# 15_-_ETHERNET_PHY.net
KiCad netlist of a schematic drawn in Altium Designer
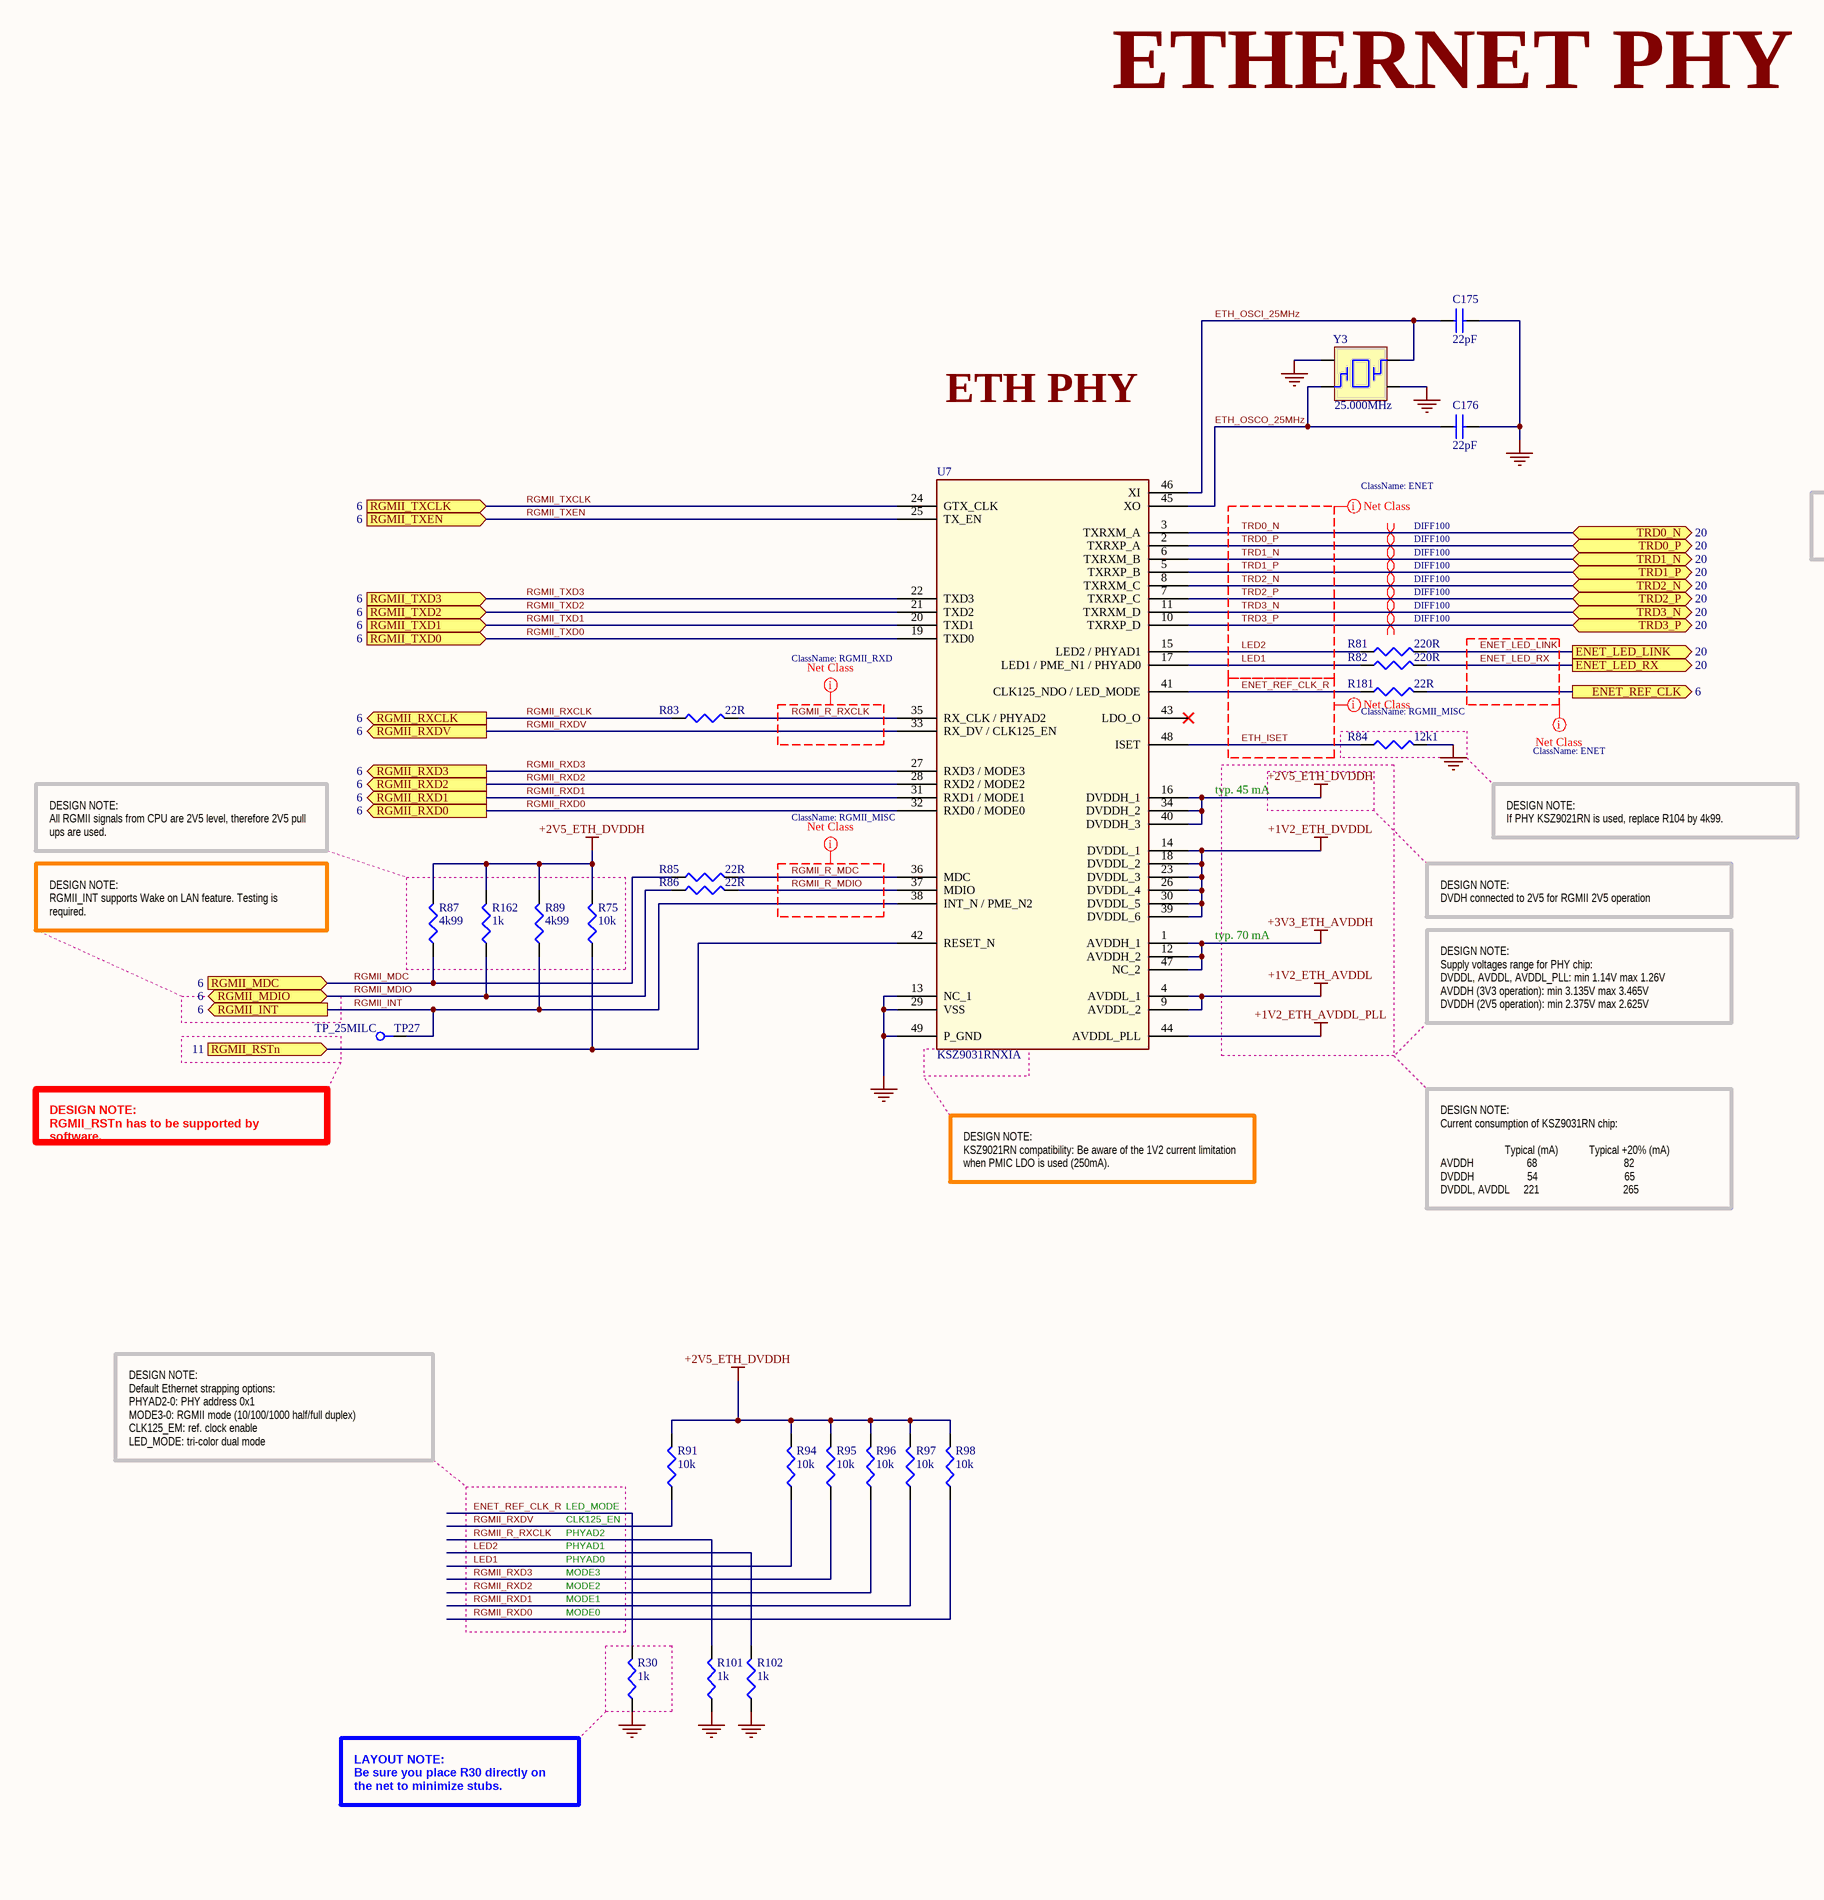
[diagram p0: [15] - ETHERNET PHY.SchDoc, left]
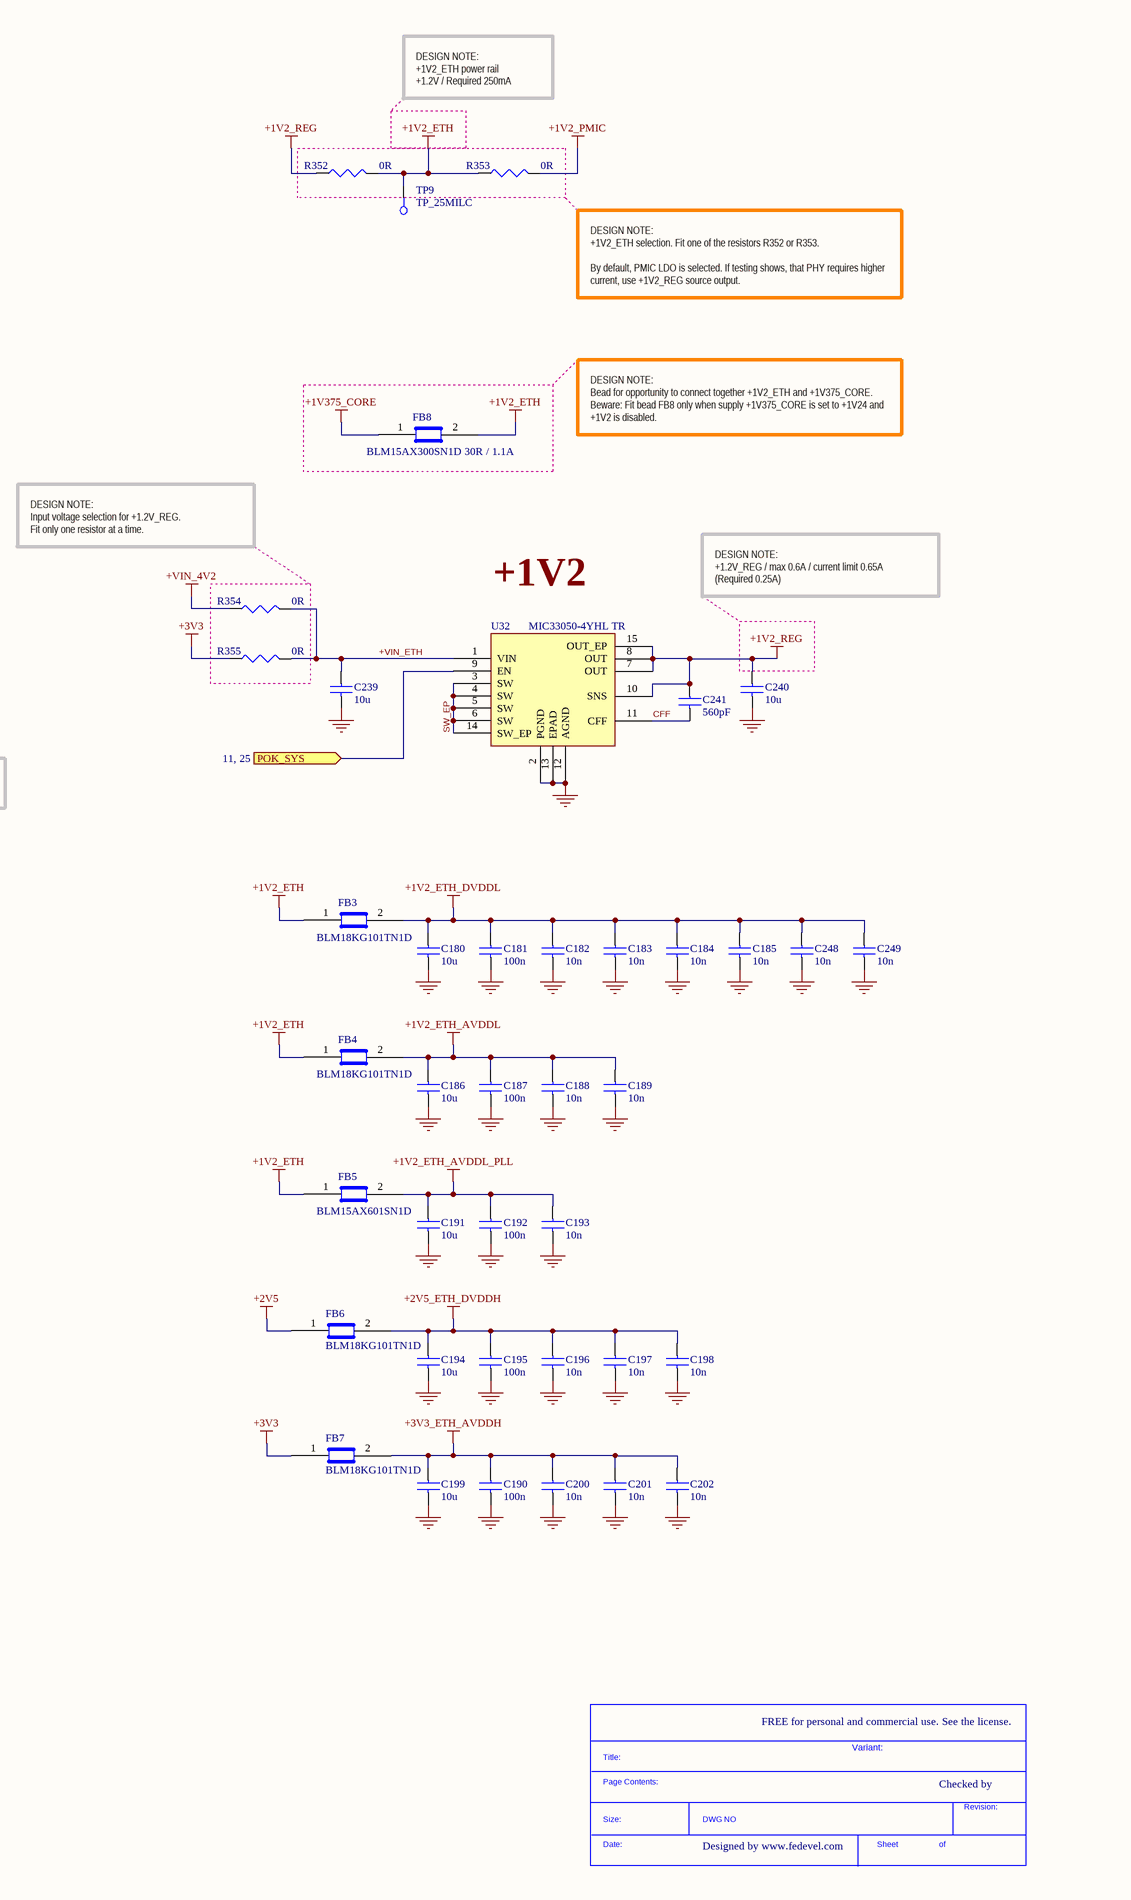
[diagram p1: [15] - ETHERNET PHY.SchDoc, right]

(export (version "E")
  (design (tool "Eeschema 10.0.6"))
  (components
    (comp (ref "C175")
      (value "22pF")
      (footprint "C0402")
      (description "CAP CER 22PF 50V C0G 5% 0402")
      (fields
        (field (name "MANUFACTURER") "TDK Corporation")
        (field (name "MANUFACTURER PART NUMBER") "C1005C0G1H220J")
      )
      (libsource (lib "Integrated_Library_FEDEVEL_APR_2015") (part "C1005C0G1H220J"))
    )
    (comp (ref "C176")
      (value "22pF")
      (footprint "C0402")
      (description "CAP CER 22PF 50V C0G 5% 0402")
      (fields
        (field (name "MANUFACTURER") "TDK Corporation")
        (field (name "MANUFACTURER PART NUMBER") "C1005C0G1H220J")
      )
      (libsource (lib "Integrated_Library_FEDEVEL_APR_2015") (part "C1005C0G1H220J"))
    )
    (comp (ref "C180")
      (value "10u")
      (footprint "C0603")
      (description "CAP CER 10UF 6.3V X5R 20% 0603")
      (fields
        (field (name "MANUFACTURER") "TDK Corporation")
        (field (name "MANUFACTURER PART NUMBER") "C1608X5R0J106M")
      )
      (libsource (lib "Integrated_Library_FEDEVEL_APR_2015") (part "C1608X5R0J106M"))
    )
    (comp (ref "C181")
      (value "100n")
      (footprint "C0402")
      (description "CAP CER .10UF 50V X5R 10% 0402")
      (fields
        (field (name "MANUFACTURER") "TDK Corporation")
        (field (name "MANUFACTURER PART NUMBER") "C1005X5R1H104K")
      )
      (libsource (lib "Integrated_Library_FEDEVEL_APR_2015") (part "C1005X5R1H104K"))
    )
    (comp (ref "C182")
      (value "10n")
      (footprint "C0402")
      (description "CAP CER 10000PF 50V 10% X7R 0402")
      (fields
        (field (name "MANUFACTURER") "TDK Corporation")
        (field (name "MANUFACTURER PART NUMBER") "C1005X7R1H103K")
      )
      (libsource (lib "Integrated_Library_FEDEVEL_APR_2015") (part "C1005X7R1H103K"))
    )
    (comp (ref "C183")
      (value "10n")
      (footprint "C0402")
      (description "CAP CER 10000PF 50V 10% X7R 0402")
      (fields
        (field (name "MANUFACTURER") "TDK Corporation")
        (field (name "MANUFACTURER PART NUMBER") "C1005X7R1H103K")
      )
      (libsource (lib "Integrated_Library_FEDEVEL_APR_2015") (part "C1005X7R1H103K"))
    )
    (comp (ref "C184")
      (value "10n")
      (footprint "C0402")
      (description "CAP CER 10000PF 50V 10% X7R 0402")
      (fields
        (field (name "MANUFACTURER") "TDK Corporation")
        (field (name "MANUFACTURER PART NUMBER") "C1005X7R1H103K")
      )
      (libsource (lib "Integrated_Library_FEDEVEL_APR_2015") (part "C1005X7R1H103K"))
    )
    (comp (ref "C185")
      (value "10n")
      (footprint "C0402")
      (description "CAP CER 10000PF 50V 10% X7R 0402")
      (fields
        (field (name "MANUFACTURER") "TDK Corporation")
        (field (name "MANUFACTURER PART NUMBER") "C1005X7R1H103K")
      )
      (libsource (lib "Integrated_Library_FEDEVEL_APR_2015") (part "C1005X7R1H103K"))
    )
    (comp (ref "C186")
      (value "10u")
      (footprint "C0603")
      (description "CAP CER 10UF 6.3V X5R 20% 0603")
      (fields
        (field (name "MANUFACTURER") "TDK Corporation")
        (field (name "MANUFACTURER PART NUMBER") "C1608X5R0J106M")
      )
      (libsource (lib "Integrated_Library_FEDEVEL_APR_2015") (part "C1608X5R0J106M"))
    )
    (comp (ref "C187")
      (value "100n")
      (footprint "C0402")
      (description "CAP CER .10UF 50V X5R 10% 0402")
      (fields
        (field (name "MANUFACTURER") "TDK Corporation")
        (field (name "MANUFACTURER PART NUMBER") "C1005X5R1H104K")
      )
      (libsource (lib "Integrated_Library_FEDEVEL_APR_2015") (part "C1005X5R1H104K"))
    )
    (comp (ref "C188")
      (value "10n")
      (footprint "C0402")
      (description "CAP CER 10000PF 50V 10% X7R 0402")
      (fields
        (field (name "MANUFACTURER") "TDK Corporation")
        (field (name "MANUFACTURER PART NUMBER") "C1005X7R1H103K")
      )
      (libsource (lib "Integrated_Library_FEDEVEL_APR_2015") (part "C1005X7R1H103K"))
    )
    (comp (ref "C189")
      (value "10n")
      (footprint "C0402")
      (description "CAP CER 10000PF 50V 10% X7R 0402")
      (fields
        (field (name "MANUFACTURER") "TDK Corporation")
        (field (name "MANUFACTURER PART NUMBER") "C1005X7R1H103K")
      )
      (libsource (lib "Integrated_Library_FEDEVEL_APR_2015") (part "C1005X7R1H103K"))
    )
    (comp (ref "C190")
      (value "100n")
      (footprint "C0402")
      (description "CAP CER .10UF 50V X5R 10% 0402")
      (fields
        (field (name "MANUFACTURER") "TDK Corporation")
        (field (name "MANUFACTURER PART NUMBER") "C1005X5R1H104K")
      )
      (libsource (lib "Integrated_Library_FEDEVEL_APR_2015") (part "C1005X5R1H104K"))
    )
    (comp (ref "C191")
      (value "10u")
      (footprint "C0603")
      (description "CAP CER 10UF 6.3V X5R 20% 0603")
      (fields
        (field (name "MANUFACTURER") "TDK Corporation")
        (field (name "MANUFACTURER PART NUMBER") "C1608X5R0J106M")
      )
      (libsource (lib "Integrated_Library_FEDEVEL_APR_2015") (part "C1608X5R0J106M"))
    )
    (comp (ref "C192")
      (value "100n")
      (footprint "C0402")
      (description "CAP CER .10UF 50V X5R 10% 0402")
      (fields
        (field (name "MANUFACTURER") "TDK Corporation")
        (field (name "MANUFACTURER PART NUMBER") "C1005X5R1H104K")
      )
      (libsource (lib "Integrated_Library_FEDEVEL_APR_2015") (part "C1005X5R1H104K"))
    )
    (comp (ref "C193")
      (value "10n")
      (footprint "C0402")
      (description "CAP CER 10000PF 50V 10% X7R 0402")
      (fields
        (field (name "MANUFACTURER") "TDK Corporation")
        (field (name "MANUFACTURER PART NUMBER") "C1005X7R1H103K")
      )
      (libsource (lib "Integrated_Library_FEDEVEL_APR_2015") (part "C1005X7R1H103K"))
    )
    (comp (ref "C194")
      (value "10u")
      (footprint "C0603")
      (description "CAP CER 10UF 6.3V X5R 20% 0603")
      (fields
        (field (name "MANUFACTURER") "TDK Corporation")
        (field (name "MANUFACTURER PART NUMBER") "C1608X5R0J106M")
      )
      (libsource (lib "Integrated_Library_FEDEVEL_APR_2015") (part "C1608X5R0J106M"))
    )
    (comp (ref "C195")
      (value "100n")
      (footprint "C0402")
      (description "CAP CER .10UF 50V X5R 10% 0402")
      (fields
        (field (name "MANUFACTURER") "TDK Corporation")
        (field (name "MANUFACTURER PART NUMBER") "C1005X5R1H104K")
      )
      (libsource (lib "Integrated_Library_FEDEVEL_APR_2015") (part "C1005X5R1H104K"))
    )
    (comp (ref "C196")
      (value "10n")
      (footprint "C0402")
      (description "CAP CER 10000PF 50V 10% X7R 0402")
      (fields
        (field (name "MANUFACTURER") "TDK Corporation")
        (field (name "MANUFACTURER PART NUMBER") "C1005X7R1H103K")
      )
      (libsource (lib "Integrated_Library_FEDEVEL_APR_2015") (part "C1005X7R1H103K"))
    )
    (comp (ref "C197")
      (value "10n")
      (footprint "C0402")
      (description "CAP CER 10000PF 50V 10% X7R 0402")
      (fields
        (field (name "MANUFACTURER") "TDK Corporation")
        (field (name "MANUFACTURER PART NUMBER") "C1005X7R1H103K")
      )
      (libsource (lib "Integrated_Library_FEDEVEL_APR_2015") (part "C1005X7R1H103K"))
    )
    (comp (ref "C198")
      (value "10n")
      (footprint "C0402")
      (description "CAP CER 10000PF 50V 10% X7R 0402")
      (fields
        (field (name "MANUFACTURER") "TDK Corporation")
        (field (name "MANUFACTURER PART NUMBER") "C1005X7R1H103K")
      )
      (libsource (lib "Integrated_Library_FEDEVEL_APR_2015") (part "C1005X7R1H103K"))
    )
    (comp (ref "C199")
      (value "10u")
      (footprint "C0603")
      (description "CAP CER 10UF 6.3V X5R 20% 0603")
      (fields
        (field (name "MANUFACTURER") "TDK Corporation")
        (field (name "MANUFACTURER PART NUMBER") "C1608X5R0J106M")
      )
      (libsource (lib "Integrated_Library_FEDEVEL_APR_2015") (part "C1608X5R0J106M"))
    )
    (comp (ref "C200")
      (value "10n")
      (footprint "C0402")
      (description "CAP CER 10000PF 50V 10% X7R 0402")
      (fields
        (field (name "MANUFACTURER") "TDK Corporation")
        (field (name "MANUFACTURER PART NUMBER") "C1005X7R1H103K")
      )
      (libsource (lib "Integrated_Library_FEDEVEL_APR_2015") (part "C1005X7R1H103K"))
    )
    (comp (ref "C201")
      (value "10n")
      (footprint "C0402")
      (description "CAP CER 10000PF 50V 10% X7R 0402")
      (fields
        (field (name "MANUFACTURER") "TDK Corporation")
        (field (name "MANUFACTURER PART NUMBER") "C1005X7R1H103K")
      )
      (libsource (lib "Integrated_Library_FEDEVEL_APR_2015") (part "C1005X7R1H103K"))
    )
    (comp (ref "C202")
      (value "10n")
      (footprint "C0402")
      (description "CAP CER 10000PF 50V 10% X7R 0402")
      (fields
        (field (name "MANUFACTURER") "TDK Corporation")
        (field (name "MANUFACTURER PART NUMBER") "C1005X7R1H103K")
      )
      (libsource (lib "Integrated_Library_FEDEVEL_APR_2015") (part "C1005X7R1H103K"))
    )
    (comp (ref "C239")
      (value "10u")
      (footprint "C0603")
      (description "CAP CER 10UF 6.3V X5R 20% 0603")
      (fields
        (field (name "MANUFACTURER") "TDK Corporation")
        (field (name "MANUFACTURER PART NUMBER") "C1608X5R0J106M")
      )
      (libsource (lib "Integrated_Library_FEDEVEL_APR_2015") (part "C1608X5R0J106M"))
    )
    (comp (ref "C240")
      (value "10u")
      (footprint "C0603")
      (description "CAP CER 10UF 6.3V X5R 20% 0603")
      (fields
        (field (name "MANUFACTURER") "TDK Corporation")
        (field (name "MANUFACTURER PART NUMBER") "C1608X5R0J106M")
      )
      (libsource (lib "Integrated_Library_FEDEVEL_APR_2015") (part "C1608X5R0J106M"))
    )
    (comp (ref "C241")
      (value "560pF")
      (footprint "C0402")
      (description "CAP CER 560PF 50V C0G 0402")
      (fields
        (field (name "MANUFACTURER") "Murata Electronics North America")
        (field (name "MANUFACTURER PART NUMBER") "GRM1555C1H561JA01D")
      )
      (libsource (lib "Integrated_Library_FEDEVEL_APR_2015") (part "GRM1555C1H561JA01D"))
    )
    (comp (ref "C248")
      (value "10n")
      (footprint "C0402")
      (description "CAP CER 10000PF 50V 10% X7R 0402")
      (fields
        (field (name "MANUFACTURER") "TDK Corporation")
        (field (name "MANUFACTURER PART NUMBER") "C1005X7R1H103K")
      )
      (libsource (lib "Integrated_Library_FEDEVEL_APR_2015") (part "C1005X7R1H103K"))
    )
    (comp (ref "C249")
      (value "10n")
      (footprint "C0402")
      (description "CAP CER 10000PF 50V 10% X7R 0402")
      (fields
        (field (name "MANUFACTURER") "TDK Corporation")
        (field (name "MANUFACTURER PART NUMBER") "C1005X7R1H103K")
      )
      (libsource (lib "Integrated_Library_FEDEVEL_APR_2015") (part "C1005X7R1H103K"))
    )
    (comp (ref "FB3")
      (value "BLM18KG101TN1D")
      (footprint "C0603")
      (description "FERRITE CHIP 100 OHM BEAD 0603 3A")
      (fields (field (name "MANUFACTURER") "Murata Electronics North America"))
      (libsource (lib "Integrated_Library_FEDEVEL_APR_2015") (part "BLM18KG101TN1D"))
    )
    (comp (ref "FB4")
      (value "BLM18KG101TN1D")
      (footprint "C0603")
      (description "FERRITE CHIP 100 OHM BEAD 0603 3A")
      (fields (field (name "MANUFACTURER") "Murata Electronics North America"))
      (libsource (lib "Integrated_Library_FEDEVEL_APR_2015") (part "BLM18KG101TN1D"))
    )
    (comp (ref "FB5")
      (value "BLM15AX601SN1D")
      (footprint "C0402")
      (description "FERRITE CHIP 600 OHM 0402 420mA")
      (fields (field (name "MANUFACTURER") "Murata Electronics North America"))
      (libsource (lib "Integrated_Library_FEDEVEL_APR_2015") (part "BLM15AX601SN1D"))
    )
    (comp (ref "FB6")
      (value "BLM18KG101TN1D")
      (footprint "C0603")
      (description "FERRITE CHIP 100 OHM BEAD 0603 3A")
      (fields (field (name "MANUFACTURER") "Murata Electronics North America"))
      (libsource (lib "Integrated_Library_FEDEVEL_APR_2015") (part "BLM18KG101TN1D"))
    )
    (comp (ref "FB7")
      (value "BLM18KG101TN1D")
      (footprint "C0603")
      (description "FERRITE CHIP 100 OHM BEAD 0603 3A")
      (fields (field (name "MANUFACTURER") "Murata Electronics North America"))
      (libsource (lib "Integrated_Library_FEDEVEL_APR_2015") (part "BLM18KG101TN1D"))
    )
    (comp (ref "FB8")
      (value "BLM15AX300SN1D 30R / 1.1A")
      (footprint "C0402")
      (description "FERRITE CHIP 30 OHM 1100MA 0402")
      (fields
        (field (name "MANUFACTURER") "Murata Electronics North America")
        (field (name "MANUFACTURER PART NUMBER") "BLM15AX300SN1D")
        (field (name ".CHECKED PCB") "MM")
        (field (name ".CHECKED SCH") "MM")
      )
      (libsource (lib "Integrated_Library_FEDEVEL_APR_2015") (part "BLM15AX300SN1D"))
    )
    (comp (ref "R30")
      (value "1k")
      (footprint "R0402")
      (description "RES 1.00K OHM 1/16W 1% 0402 SMD")
      (fields
        (field (name "MANUFACTURER") "Yageo")
        (field (name "MANUFACTURER PART NUMBER") "RC0402FR-071KL")
      )
      (libsource (lib "Integrated_Library_FEDEVEL_APR_2015") (part "RC0402FR-071KL"))
    )
    (comp (ref "R75")
      (value "10k")
      (footprint "R0402")
      (description "RES 10.0K OHM 1/16W 1% 0402 SMD")
      (fields
        (field (name "MANUFACTURER") "Yageo")
        (field (name "MANUFACTURER PART NUMBER") "RC0402FR-0710KL")
      )
      (libsource (lib "Integrated_Library_FEDEVEL_APR_2015") (part "RC0402FR-0710KL"))
    )
    (comp (ref "R81")
      (value "220R")
      (footprint "R0402")
      (description "RES 220 OHM 1/16W 1% 0402 SMD")
      (fields
        (field (name "MANUFACTURER") "Yageo")
        (field (name "MANUFACTURER PART NUMBER") "RC0402FR-07220RL")
      )
      (libsource (lib "Integrated_Library_FEDEVEL_APR_2015") (part "RC0402FR-07220RL"))
    )
    (comp (ref "R82")
      (value "220R")
      (footprint "R0402")
      (description "RES 220 OHM 1/16W 1% 0402 SMD")
      (fields
        (field (name "MANUFACTURER") "Yageo")
        (field (name "MANUFACTURER PART NUMBER") "RC0402FR-07220RL")
      )
      (libsource (lib "Integrated_Library_FEDEVEL_APR_2015") (part "RC0402FR-07220RL"))
    )
    (comp (ref "R83")
      (value "22R")
      (footprint "R0402")
      (description "RES 22.0 OHM 1/16W 1% 0402 SMD")
      (fields
        (field (name "MANUFACTURER") "Yageo")
        (field (name "MANUFACTURER PART NUMBER") "RC0402FR-0722RL")
      )
      (libsource (lib "Integrated_Library_FEDEVEL_APR_2015") (part "RC0402FR-0722RL"))
    )
    (comp (ref "R84")
      (value "12k1")
      (footprint "R0402")
      (description "RES SMD 12.1K OHM 1% 1/16W 0402")
      (fields
        (field (name "MANUFACTURER") "Yageo")
        (field (name "MANUFACTURER PART NUMBER") "RC0402FR-0712K1L")
        (field (name ".CREATOR") "MM")
        (field (name ".CHECKED PCB") "MM")
        (field (name ".CHECKED SCH") "MM")
      )
      (libsource (lib "Integrated_Library_FEDEVEL_APR_2015") (part "RC0402FR-0712K1L"))
    )
    (comp (ref "R85")
      (value "22R")
      (footprint "R0402")
      (description "RES 22.0 OHM 1/16W 1% 0402 SMD")
      (fields
        (field (name "MANUFACTURER") "Yageo")
        (field (name "MANUFACTURER PART NUMBER") "RC0402FR-0722RL")
      )
      (libsource (lib "Integrated_Library_FEDEVEL_APR_2015") (part "RC0402FR-0722RL"))
    )
    (comp (ref "R86")
      (value "22R")
      (footprint "R0402")
      (description "RES 22.0 OHM 1/16W 1% 0402 SMD")
      (fields
        (field (name "MANUFACTURER") "Yageo")
        (field (name "MANUFACTURER PART NUMBER") "RC0402FR-0722RL")
      )
      (libsource (lib "Integrated_Library_FEDEVEL_APR_2015") (part "RC0402FR-0722RL"))
    )
    (comp (ref "R87")
      (value "4k99")
      (footprint "R0402")
      (description "RES TF 4.99K OHM 1% 1/16W 0402")
      (fields
        (field (name "MANUFACTURER") "Stackpole Electronics Inc")
        (field (name "MANUFACTURER PART NUMBER") "RMCF0402FT4K99")
      )
      (libsource (lib "Integrated_Library_FEDEVEL_APR_2015") (part "RMCF0402FT4K99"))
    )
    (comp (ref "R89")
      (value "4k99")
      (footprint "R0402")
      (description "RES TF 4.99K OHM 1% 1/16W 0402")
      (fields
        (field (name "MANUFACTURER") "Stackpole Electronics Inc")
        (field (name "MANUFACTURER PART NUMBER") "RMCF0402FT4K99")
      )
      (libsource (lib "Integrated_Library_FEDEVEL_APR_2015") (part "RMCF0402FT4K99"))
    )
    (comp (ref "R91")
      (value "10k")
      (footprint "R0402")
      (description "RES 10.0K OHM 1/16W 1% 0402 SMD")
      (fields
        (field (name "MANUFACTURER") "Yageo")
        (field (name "MANUFACTURER PART NUMBER") "RC0402FR-0710KL")
      )
      (libsource (lib "Integrated_Library_FEDEVEL_APR_2015") (part "RC0402FR-0710KL"))
    )
    (comp (ref "R94")
      (value "10k")
      (footprint "R0402")
      (description "RES 10.0K OHM 1/16W 1% 0402 SMD")
      (fields
        (field (name "MANUFACTURER") "Yageo")
        (field (name "MANUFACTURER PART NUMBER") "RC0402FR-0710KL")
      )
      (libsource (lib "Integrated_Library_FEDEVEL_APR_2015") (part "RC0402FR-0710KL"))
    )
    (comp (ref "R95")
      (value "10k")
      (footprint "R0402")
      (description "RES 10.0K OHM 1/16W 1% 0402 SMD")
      (fields
        (field (name "MANUFACTURER") "Yageo")
        (field (name "MANUFACTURER PART NUMBER") "RC0402FR-0710KL")
      )
      (libsource (lib "Integrated_Library_FEDEVEL_APR_2015") (part "RC0402FR-0710KL"))
    )
    (comp (ref "R96")
      (value "10k")
      (footprint "R0402")
      (description "RES 10.0K OHM 1/16W 1% 0402 SMD")
      (fields
        (field (name "MANUFACTURER") "Yageo")
        (field (name "MANUFACTURER PART NUMBER") "RC0402FR-0710KL")
      )
      (libsource (lib "Integrated_Library_FEDEVEL_APR_2015") (part "RC0402FR-0710KL"))
    )
    (comp (ref "R97")
      (value "10k")
      (footprint "R0402")
      (description "RES 10.0K OHM 1/16W 1% 0402 SMD")
      (fields
        (field (name "MANUFACTURER") "Yageo")
        (field (name "MANUFACTURER PART NUMBER") "RC0402FR-0710KL")
      )
      (libsource (lib "Integrated_Library_FEDEVEL_APR_2015") (part "RC0402FR-0710KL"))
    )
    (comp (ref "R98")
      (value "10k")
      (footprint "R0402")
      (description "RES 10.0K OHM 1/16W 1% 0402 SMD")
      (fields
        (field (name "MANUFACTURER") "Yageo")
        (field (name "MANUFACTURER PART NUMBER") "RC0402FR-0710KL")
      )
      (libsource (lib "Integrated_Library_FEDEVEL_APR_2015") (part "RC0402FR-0710KL"))
    )
    (comp (ref "R101")
      (value "1k")
      (footprint "R0402")
      (description "RES 1.00K OHM 1/16W 1% 0402 SMD")
      (fields
        (field (name "MANUFACTURER") "Yageo")
        (field (name "MANUFACTURER PART NUMBER") "RC0402FR-071KL")
      )
      (libsource (lib "Integrated_Library_FEDEVEL_APR_2015") (part "RC0402FR-071KL"))
    )
    (comp (ref "R102")
      (value "1k")
      (footprint "R0402")
      (description "RES 1.00K OHM 1/16W 1% 0402 SMD")
      (fields
        (field (name "MANUFACTURER") "Yageo")
        (field (name "MANUFACTURER PART NUMBER") "RC0402FR-071KL")
      )
      (libsource (lib "Integrated_Library_FEDEVEL_APR_2015") (part "RC0402FR-071KL"))
    )
    (comp (ref "R162")
      (value "1k")
      (footprint "R0402")
      (description "RES 1.00K OHM 1/16W 1% 0402 SMD")
      (fields
        (field (name "MANUFACTURER") "Yageo")
        (field (name "MANUFACTURER PART NUMBER") "RC0402FR-071KL")
      )
      (libsource (lib "Integrated_Library_FEDEVEL_APR_2015") (part "RC0402FR-071KL"))
    )
    (comp (ref "R181")
      (value "22R")
      (footprint "R0402")
      (description "RES 22.0 OHM 1/16W 1% 0402 SMD")
      (fields
        (field (name "MANUFACTURER") "Yageo")
        (field (name "MANUFACTURER PART NUMBER") "RC0402FR-0722RL")
      )
      (libsource (lib "Integrated_Library_FEDEVEL_APR_2015") (part "RC0402FR-0722RL"))
    )
    (comp (ref "R352")
      (value "0R")
      (footprint "R0402")
      (description "RES 0.0 OHM 1/16W 0402 SMD")
      (fields
        (field (name "MANUFACTURER") "Yageo")
        (field (name "MANUFACTURER PART NUMBER") "RC0402JR-070RL")
      )
      (libsource (lib "Integrated_Library_FEDEVEL_APR_2015") (part "RC0402JR-070RL"))
    )
    (comp (ref "R353")
      (value "0R")
      (footprint "R0402")
      (description "RES 0.0 OHM 1/16W 0402 SMD")
      (fields
        (field (name "MANUFACTURER") "Yageo")
        (field (name "MANUFACTURER PART NUMBER") "RC0402JR-070RL")
      )
      (libsource (lib "Integrated_Library_FEDEVEL_APR_2015") (part "RC0402JR-070RL"))
    )
    (comp (ref "R354")
      (value "0R")
      (footprint "R0402")
      (description "RES 0.0 OHM 1/16W 0402 SMD")
      (fields
        (field (name "MANUFACTURER") "Yageo")
        (field (name "MANUFACTURER PART NUMBER") "RC0402JR-070RL")
      )
      (libsource (lib "Integrated_Library_FEDEVEL_APR_2015") (part "RC0402JR-070RL"))
    )
    (comp (ref "R355")
      (value "0R")
      (footprint "R0402")
      (description "RES 0.0 OHM 1/16W 0402 SMD")
      (fields
        (field (name "MANUFACTURER") "Yageo")
        (field (name "MANUFACTURER PART NUMBER") "RC0402JR-070RL")
      )
      (libsource (lib "Integrated_Library_FEDEVEL_APR_2015") (part "RC0402JR-070RL"))
    )
    (comp (ref "TP9")
      (value "TP_25MILC")
      (footprint "TP_25C")
      (description "Test Point 25mil")
      (libsource (lib "Integrated_Library_FEDEVEL_APR_2015") (part "TP_25MILC"))
    )
    (comp (ref "TP27")
      (value "TP_25MILC")
      (footprint "TP_25C")
      (description "Test Point 25mil")
      (libsource (lib "Integrated_Library_FEDEVEL_APR_2015") (part "TP_25MILC"))
    )
    (comp (ref "U7")
      (value "KSZ9031RNXIA")
      (footprint "QFN48_SMALL_EP_7MMX7MM")
      (description "IC TXRX ETHERNET 48-QFN")
      (fields
        (field (name "MANUFACTURER") "Micrel Inc")
        (field (name ".CREATOR") "MM")
        (field (name ".CHECKED PCB") "MM")
        (field (name ".CHECKED SCH") "MM")
      )
      (libsource (lib "Integrated_Library_FEDEVEL_APR_2015") (part "KSZ9031RNXIA"))
    )
    (comp (ref "U32")
      (value "MIC33050-4YHL TR")
      (footprint "MLF_3x3_12PINS")
      (description "IC PWM REG 600mA 1.2V 12-MLF")
      (fields (field (name "MANUFACTURER") "Micrel Inc"))
      (libsource (lib "Integrated_Library_FEDEVEL_APR_2015") (part "MIC33050-4YHL TR"))
    )
    (comp (ref "Y3")
      (value "25.000MHz")
      (footprint "ABM8G")
      (description "CRYSTAL 25MHZ 18PF SMD")
      (fields
        (field (name "MANUFACTURER") "Abracon Corporation")
        (field (name "MANUFACTURER PART NUMBER") "ABM8G-25.000MHZ-18-D2Y-T")
        (field (name ".CHECKED PCB") "MM")
        (field (name ".CHECKED SCH") "MM")
        (field (name ".CREATOR") "MM")
      )
      (libsource (lib "Integrated_Library_FEDEVEL_APR_2015") (part "ABM8G-25.000MHZ-18-D2Y-T"))
    )
  )
  (nets
    (net (code "1") (name "+1V2_ETH") (class "Default")
      (node (ref "FB3") (pin "1") (pinfunction "1_1") (pintype "passive"))
      (node (ref "FB4") (pin "1") (pinfunction "1_1") (pintype "passive"))
      (node (ref "FB5") (pin "1") (pinfunction "1_1") (pintype "passive"))
      (node (ref "FB8") (pin "2") (pinfunction "2_2") (pintype "passive"))
      (node (ref "R352") (pin "2") (pinfunction "2_2") (pintype "passive"))
      (node (ref "R353") (pin "1") (pinfunction "1_1") (pintype "passive"))
      (node (ref "TP9") (pin "1") (pinfunction "1_1") (pintype "passive"))
    )
    (net (code "2") (name "+1V2_ETH_AVDDL") (class "Default")
      (node (ref "C186") (pin "1") (pinfunction "1_1") (pintype "passive"))
      (node (ref "C187") (pin "1") (pinfunction "1_1") (pintype "passive"))
      (node (ref "C188") (pin "1") (pinfunction "1_1") (pintype "passive"))
      (node (ref "C189") (pin "1") (pinfunction "1_1") (pintype "passive"))
      (node (ref "FB4") (pin "2") (pinfunction "2_2") (pintype "passive"))
      (node (ref "U7") (pin "4") (pinfunction "AVDDL_1_4") (pintype "passive"))
      (node (ref "U7") (pin "9") (pinfunction "AVDDL_2_9") (pintype "passive"))
    )
    (net (code "3") (name "+1V2_ETH_AVDDL_PLL") (class "Default")
      (node (ref "C191") (pin "1") (pinfunction "1_1") (pintype "passive"))
      (node (ref "C192") (pin "1") (pinfunction "1_1") (pintype "passive"))
      (node (ref "C193") (pin "1") (pinfunction "1_1") (pintype "passive"))
      (node (ref "FB5") (pin "2") (pinfunction "2_2") (pintype "passive"))
      (node (ref "U7") (pin "44") (pinfunction "AVDDL_PLL_44") (pintype "passive"))
    )
    (net (code "4") (name "+1V2_ETH_DVDDL") (class "Default")
      (node (ref "C180") (pin "1") (pinfunction "1_1") (pintype "passive"))
      (node (ref "C181") (pin "1") (pinfunction "1_1") (pintype "passive"))
      (node (ref "C182") (pin "1") (pinfunction "1_1") (pintype "passive"))
      (node (ref "C183") (pin "1") (pinfunction "1_1") (pintype "passive"))
      (node (ref "C184") (pin "1") (pinfunction "1_1") (pintype "passive"))
      (node (ref "C185") (pin "1") (pinfunction "1_1") (pintype "passive"))
      (node (ref "C248") (pin "1") (pinfunction "1_1") (pintype "passive"))
      (node (ref "C249") (pin "1") (pinfunction "1_1") (pintype "passive"))
      (node (ref "FB3") (pin "2") (pinfunction "2_2") (pintype "passive"))
      (node (ref "U7") (pin "14") (pinfunction "DVDDL_1_14") (pintype "passive"))
      (node (ref "U7") (pin "18") (pinfunction "DVDDL_2_18") (pintype "passive"))
      (node (ref "U7") (pin "23") (pinfunction "DVDDL_3_23") (pintype "passive"))
      (node (ref "U7") (pin "26") (pinfunction "DVDDL_4_26") (pintype "passive"))
      (node (ref "U7") (pin "30") (pinfunction "DVDDL_5_30") (pintype "passive"))
      (node (ref "U7") (pin "39") (pinfunction "DVDDL_6_39") (pintype "passive"))
    )
    (net (code "5") (name "+1V2_PMIC") (class "Default")
      (node (ref "R353") (pin "2") (pinfunction "2_2") (pintype "passive"))
    )
    (net (code "6") (name "+1V2_REG") (class "Default")
      (node (ref "C240") (pin "1") (pinfunction "1_1") (pintype "passive"))
      (node (ref "C241") (pin "1") (pinfunction "1_1") (pintype "passive"))
      (node (ref "R352") (pin "1") (pinfunction "1_1") (pintype "passive"))
      (node (ref "U32") (pin "10") (pinfunction "SNS_10") (pintype "passive"))
      (node (ref "U32") (pin "15") (pinfunction "OUT_EP_15") (pintype "passive"))
      (node (ref "U32") (pin "7") (pinfunction "OUT_7") (pintype "passive"))
      (node (ref "U32") (pin "8") (pinfunction "OUT_8") (pintype "passive"))
    )
    (net (code "7") (name "+1V375_CORE") (class "Default")
      (node (ref "FB8") (pin "1") (pinfunction "1_1") (pintype "passive"))
    )
    (net (code "8") (name "+2V5") (class "Default")
      (node (ref "FB6") (pin "1") (pinfunction "1_1") (pintype "passive"))
    )
    (net (code "9") (name "+2V5_ETH_DVDDH") (class "Default")
      (node (ref "C194") (pin "1") (pinfunction "1_1") (pintype "passive"))
      (node (ref "C195") (pin "1") (pinfunction "1_1") (pintype "passive"))
      (node (ref "C196") (pin "1") (pinfunction "1_1") (pintype "passive"))
      (node (ref "C197") (pin "1") (pinfunction "1_1") (pintype "passive"))
      (node (ref "C198") (pin "1") (pinfunction "1_1") (pintype "passive"))
      (node (ref "FB6") (pin "2") (pinfunction "2_2") (pintype "passive"))
      (node (ref "R162") (pin "2") (pinfunction "2_2") (pintype "passive"))
      (node (ref "R75") (pin "2") (pinfunction "2_2") (pintype "passive"))
      (node (ref "R87") (pin "2") (pinfunction "2_2") (pintype "passive"))
      (node (ref "R89") (pin "2") (pinfunction "2_2") (pintype "passive"))
      (node (ref "R91") (pin "2") (pinfunction "2_2") (pintype "passive"))
      (node (ref "R94") (pin "2") (pinfunction "2_2") (pintype "passive"))
      (node (ref "R95") (pin "2") (pinfunction "2_2") (pintype "passive"))
      (node (ref "R96") (pin "2") (pinfunction "2_2") (pintype "passive"))
      (node (ref "R97") (pin "2") (pinfunction "2_2") (pintype "passive"))
      (node (ref "R98") (pin "2") (pinfunction "2_2") (pintype "passive"))
      (node (ref "U7") (pin "16") (pinfunction "DVDDH_1_16") (pintype "passive"))
      (node (ref "U7") (pin "34") (pinfunction "DVDDH_2_34") (pintype "passive"))
      (node (ref "U7") (pin "40") (pinfunction "DVDDH_3_40") (pintype "passive"))
    )
    (net (code "10") (name "+3V3") (class "Default")
      (node (ref "FB7") (pin "1") (pinfunction "1_1") (pintype "passive"))
      (node (ref "R355") (pin "1") (pinfunction "1_1") (pintype "passive"))
    )
    (net (code "11") (name "+3V3_ETH_AVDDH") (class "Default")
      (node (ref "C190") (pin "1") (pinfunction "1_1") (pintype "passive"))
      (node (ref "C199") (pin "1") (pinfunction "1_1") (pintype "passive"))
      (node (ref "C200") (pin "1") (pinfunction "1_1") (pintype "passive"))
      (node (ref "C201") (pin "1") (pinfunction "1_1") (pintype "passive"))
      (node (ref "C202") (pin "1") (pinfunction "1_1") (pintype "passive"))
      (node (ref "FB7") (pin "2") (pinfunction "2_2") (pintype "passive"))
      (node (ref "U7") (pin "1") (pinfunction "AVDDH_1_1") (pintype "passive"))
      (node (ref "U7") (pin "12") (pinfunction "AVDDH_2_12") (pintype "passive"))
      (node (ref "U7") (pin "47") (pinfunction "NC_2_47") (pintype "passive"))
    )
    (net (code "12") (name "+VIN_4V2") (class "Default")
      (node (ref "R354") (pin "1") (pinfunction "1_1") (pintype "passive"))
    )
    (net (code "13") (name "/+VIN_ETH") (class "Default")
      (node (ref "C239") (pin "1") (pinfunction "1_1") (pintype "passive"))
      (node (ref "R354") (pin "2") (pinfunction "2_2") (pintype "passive"))
      (node (ref "R355") (pin "2") (pinfunction "2_2") (pintype "passive"))
      (node (ref "U32") (pin "1") (pinfunction "VIN_1") (pintype "passive"))
    )
    (net (code "14") (name "/CFF") (class "Default")
      (node (ref "C241") (pin "2") (pinfunction "2_2") (pintype "passive"))
      (node (ref "U32") (pin "11") (pinfunction "CFF_11") (pintype "passive"))
    )
    (net (code "15") (name "/ENET_LED_LINK") (class "Default")
      (node (ref "R81") (pin "2") (pinfunction "2_2") (pintype "passive"))
    )
    (net (code "16") (name "/ENET_LED_RX") (class "Default")
      (node (ref "R82") (pin "2") (pinfunction "2_2") (pintype "passive"))
    )
    (net (code "17") (name "/ENET_REF_CLK") (class "Default")
      (node (ref "R181") (pin "2") (pinfunction "2_2") (pintype "passive"))
    )
    (net (code "18") (name "/ENET_REF_CLK_R") (class "Default")
      (node (ref "R181") (pin "1") (pinfunction "1_1") (pintype "passive"))
      (node (ref "R30") (pin "2") (pinfunction "2_2") (pintype "passive"))
      (node (ref "U7") (pin "41") (pinfunction "CLK125_NDO_/_LED_MODE_41") (pintype "passive"))
    )
    (net (code "19") (name "/ETH_ISET") (class "Default")
      (node (ref "R84") (pin "1") (pinfunction "1_1") (pintype "passive"))
      (node (ref "U7") (pin "48") (pinfunction "ISET_48") (pintype "passive"))
    )
    (net (code "20") (name "/ETH_OSCI_25MHz") (class "Default")
      (node (ref "C175") (pin "1") (pinfunction "1_1") (pintype "passive"))
      (node (ref "U7") (pin "46") (pinfunction "XI_46") (pintype "passive"))
      (node (ref "Y3") (pin "3") (pinfunction "3_3") (pintype "passive"))
    )
    (net (code "21") (name "/ETH_OSCO_25MHz") (class "Default")
      (node (ref "C176") (pin "1") (pinfunction "1_1") (pintype "passive"))
      (node (ref "U7") (pin "45") (pinfunction "XO_45") (pintype "passive"))
      (node (ref "Y3") (pin "1") (pinfunction "1_1") (pintype "passive"))
    )
    (net (code "22") (name "/LED1") (class "Default")
      (node (ref "R82") (pin "1") (pinfunction "1_1") (pintype "passive"))
      (node (ref "R94") (pin "1") (pinfunction "1_1") (pintype "passive"))
      (node (ref "U7") (pin "17") (pinfunction "LED1_/_PME_N1_/_PHYAD0_17") (pintype "passive"))
    )
    (net (code "23") (name "/LED2") (class "Default")
      (node (ref "R102") (pin "2") (pinfunction "2_2") (pintype "passive"))
      (node (ref "R81") (pin "1") (pinfunction "1_1") (pintype "passive"))
      (node (ref "U7") (pin "15") (pinfunction "LED2_/_PHYAD1_15") (pintype "passive"))
    )
    (net (code "24") (name "/POK_SYS") (class "Default")
      (node (ref "U32") (pin "9") (pinfunction "EN_9") (pintype "passive"))
    )
    (net (code "25") (name "/RGMII_INT") (class "Default")
      (node (ref "R89") (pin "1") (pinfunction "1_1") (pintype "passive"))
      (node (ref "TP27") (pin "1") (pinfunction "1_1") (pintype "passive"))
      (node (ref "U7") (pin "38") (pinfunction "INT_N_/_PME_N2_38") (pintype "passive"))
    )
    (net (code "26") (name "/RGMII_MDC") (class "Default")
      (node (ref "R85") (pin "1") (pinfunction "1_1") (pintype "passive"))
      (node (ref "R87") (pin "1") (pinfunction "1_1") (pintype "passive"))
    )
    (net (code "27") (name "/RGMII_MDIO") (class "Default")
      (node (ref "R162") (pin "1") (pinfunction "1_1") (pintype "passive"))
      (node (ref "R86") (pin "1") (pinfunction "1_1") (pintype "passive"))
    )
    (net (code "28") (name "/RGMII_RSTn") (class "Default")
      (node (ref "R75") (pin "1") (pinfunction "1_1") (pintype "passive"))
      (node (ref "U7") (pin "42") (pinfunction "RESET_N_42") (pintype "passive"))
    )
    (net (code "29") (name "/RGMII_RXCLK") (class "Default")
      (node (ref "R83") (pin "1") (pinfunction "1_1") (pintype "passive"))
    )
    (net (code "30") (name "/RGMII_RXD0") (class "Default")
      (node (ref "R98") (pin "1") (pinfunction "1_1") (pintype "passive"))
      (node (ref "U7") (pin "32") (pinfunction "RXD0_/_MODE0_32") (pintype "passive"))
    )
    (net (code "31") (name "/RGMII_RXD1") (class "Default")
      (node (ref "R97") (pin "1") (pinfunction "1_1") (pintype "passive"))
      (node (ref "U7") (pin "31") (pinfunction "RXD1_/_MODE1_31") (pintype "passive"))
    )
    (net (code "32") (name "/RGMII_RXD2") (class "Default")
      (node (ref "R96") (pin "1") (pinfunction "1_1") (pintype "passive"))
      (node (ref "U7") (pin "28") (pinfunction "RXD2_/_MODE2_28") (pintype "passive"))
    )
    (net (code "33") (name "/RGMII_RXD3") (class "Default")
      (node (ref "R95") (pin "1") (pinfunction "1_1") (pintype "passive"))
      (node (ref "U7") (pin "27") (pinfunction "RXD3_/_MODE3_27") (pintype "passive"))
    )
    (net (code "34") (name "/RGMII_RXDV") (class "Default")
      (node (ref "R91") (pin "1") (pinfunction "1_1") (pintype "passive"))
      (node (ref "U7") (pin "33") (pinfunction "RX_DV_/_CLK125_EN_33") (pintype "passive"))
    )
    (net (code "35") (name "/RGMII_R_MDC") (class "Default")
      (node (ref "R85") (pin "2") (pinfunction "2_2") (pintype "passive"))
      (node (ref "U7") (pin "36") (pinfunction "MDC_36") (pintype "passive"))
    )
    (net (code "36") (name "/RGMII_R_MDIO") (class "Default")
      (node (ref "R86") (pin "2") (pinfunction "2_2") (pintype "passive"))
      (node (ref "U7") (pin "37") (pinfunction "MDIO_37") (pintype "passive"))
    )
    (net (code "37") (name "/RGMII_R_RXCLK") (class "Default")
      (node (ref "R101") (pin "2") (pinfunction "2_2") (pintype "passive"))
      (node (ref "R83") (pin "2") (pinfunction "2_2") (pintype "passive"))
      (node (ref "U7") (pin "35") (pinfunction "RX_CLK_/_PHYAD2_35") (pintype "passive"))
    )
    (net (code "38") (name "/RGMII_TXCLK") (class "Default")
      (node (ref "U7") (pin "24") (pinfunction "GTX_CLK_24") (pintype "passive"))
    )
    (net (code "39") (name "/RGMII_TXD0") (class "Default")
      (node (ref "U7") (pin "19") (pinfunction "TXD0_19") (pintype "passive"))
    )
    (net (code "40") (name "/RGMII_TXD1") (class "Default")
      (node (ref "U7") (pin "20") (pinfunction "TXD1_20") (pintype "passive"))
    )
    (net (code "41") (name "/RGMII_TXD2") (class "Default")
      (node (ref "U7") (pin "21") (pinfunction "TXD2_21") (pintype "passive"))
    )
    (net (code "42") (name "/RGMII_TXD3") (class "Default")
      (node (ref "U7") (pin "22") (pinfunction "TXD3_22") (pintype "passive"))
    )
    (net (code "43") (name "/RGMII_TXEN") (class "Default")
      (node (ref "U7") (pin "25") (pinfunction "TX_EN_25") (pintype "passive"))
    )
    (net (code "44") (name "/SW_EP") (class "Default")
      (node (ref "U32") (pin "14") (pinfunction "SW_EP_14") (pintype "passive"))
      (node (ref "U32") (pin "3") (pinfunction "SW_3") (pintype "passive"))
      (node (ref "U32") (pin "4") (pinfunction "SW_4") (pintype "passive"))
      (node (ref "U32") (pin "5") (pinfunction "SW_5") (pintype "passive"))
      (node (ref "U32") (pin "6") (pinfunction "SW_6") (pintype "passive"))
    )
    (net (code "45") (name "/TRD0_N") (class "Default")
      (node (ref "U7") (pin "3") (pinfunction "TXRXM_A_3") (pintype "passive"))
    )
    (net (code "46") (name "/TRD0_P") (class "Default")
      (node (ref "U7") (pin "2") (pinfunction "TXRXP_A_2") (pintype "passive"))
    )
    (net (code "47") (name "/TRD1_N") (class "Default")
      (node (ref "U7") (pin "6") (pinfunction "TXRXM_B_6") (pintype "passive"))
    )
    (net (code "48") (name "/TRD1_P") (class "Default")
      (node (ref "U7") (pin "5") (pinfunction "TXRXP_B_5") (pintype "passive"))
    )
    (net (code "49") (name "/TRD2_N") (class "Default")
      (node (ref "U7") (pin "8") (pinfunction "TXRXM_C_8") (pintype "passive"))
    )
    (net (code "50") (name "/TRD2_P") (class "Default")
      (node (ref "U7") (pin "7") (pinfunction "TXRXP_C_7") (pintype "passive"))
    )
    (net (code "51") (name "/TRD3_N") (class "Default")
      (node (ref "U7") (pin "11") (pinfunction "TXRXM_D_11") (pintype "passive"))
    )
    (net (code "52") (name "/TRD3_P") (class "Default")
      (node (ref "U7") (pin "10") (pinfunction "TXRXP_D_10") (pintype "passive"))
    )
    (net (code "53") (name "GND") (class "Default")
      (node (ref "C175") (pin "2") (pinfunction "2_2") (pintype "passive"))
      (node (ref "C176") (pin "2") (pinfunction "2_2") (pintype "passive"))
      (node (ref "C180") (pin "2") (pinfunction "2_2") (pintype "passive"))
      (node (ref "C181") (pin "2") (pinfunction "2_2") (pintype "passive"))
      (node (ref "C182") (pin "2") (pinfunction "2_2") (pintype "passive"))
      (node (ref "C183") (pin "2") (pinfunction "2_2") (pintype "passive"))
      (node (ref "C184") (pin "2") (pinfunction "2_2") (pintype "passive"))
      (node (ref "C185") (pin "2") (pinfunction "2_2") (pintype "passive"))
      (node (ref "C186") (pin "2") (pinfunction "2_2") (pintype "passive"))
      (node (ref "C187") (pin "2") (pinfunction "2_2") (pintype "passive"))
      (node (ref "C188") (pin "2") (pinfunction "2_2") (pintype "passive"))
      (node (ref "C189") (pin "2") (pinfunction "2_2") (pintype "passive"))
      (node (ref "C190") (pin "2") (pinfunction "2_2") (pintype "passive"))
      (node (ref "C191") (pin "2") (pinfunction "2_2") (pintype "passive"))
      (node (ref "C192") (pin "2") (pinfunction "2_2") (pintype "passive"))
      (node (ref "C193") (pin "2") (pinfunction "2_2") (pintype "passive"))
      (node (ref "C194") (pin "2") (pinfunction "2_2") (pintype "passive"))
      (node (ref "C195") (pin "2") (pinfunction "2_2") (pintype "passive"))
      (node (ref "C196") (pin "2") (pinfunction "2_2") (pintype "passive"))
      (node (ref "C197") (pin "2") (pinfunction "2_2") (pintype "passive"))
      (node (ref "C198") (pin "2") (pinfunction "2_2") (pintype "passive"))
      (node (ref "C199") (pin "2") (pinfunction "2_2") (pintype "passive"))
      (node (ref "C200") (pin "2") (pinfunction "2_2") (pintype "passive"))
      (node (ref "C201") (pin "2") (pinfunction "2_2") (pintype "passive"))
      (node (ref "C202") (pin "2") (pinfunction "2_2") (pintype "passive"))
      (node (ref "C239") (pin "2") (pinfunction "2_2") (pintype "passive"))
      (node (ref "C240") (pin "2") (pinfunction "2_2") (pintype "passive"))
      (node (ref "C248") (pin "2") (pinfunction "2_2") (pintype "passive"))
      (node (ref "C249") (pin "2") (pinfunction "2_2") (pintype "passive"))
      (node (ref "R101") (pin "1") (pinfunction "1_1") (pintype "passive"))
      (node (ref "R102") (pin "1") (pinfunction "1_1") (pintype "passive"))
      (node (ref "R30") (pin "1") (pinfunction "1_1") (pintype "passive"))
      (node (ref "R84") (pin "2") (pinfunction "2_2") (pintype "passive"))
      (node (ref "U32") (pin "12") (pinfunction "AGND_12") (pintype "passive"))
      (node (ref "U32") (pin "13") (pinfunction "EPAD_13") (pintype "passive"))
      (node (ref "U32") (pin "2") (pinfunction "PGND_2") (pintype "passive"))
      (node (ref "U7") (pin "13") (pinfunction "NC_1_13") (pintype "passive"))
      (node (ref "U7") (pin "29") (pinfunction "VSS_29") (pintype "passive"))
      (node (ref "U7") (pin "49") (pinfunction "P_GND_49") (pintype "passive"))
      (node (ref "Y3") (pin "2") (pinfunction "2_2") (pintype "passive"))
      (node (ref "Y3") (pin "4") (pinfunction "4_4") (pintype "passive"))
    )
    (net (code "54") (name "unconnected-(U7-LDO_O-Pad43)") (class "Default")
      (node (ref "U7") (pin "43") (pinfunction "LDO_O_43") (pintype "passive+no_connect"))
    )
  )
)
